# KELU1-0234.net
KiCad netlist of a schematic drawn in EAGLE
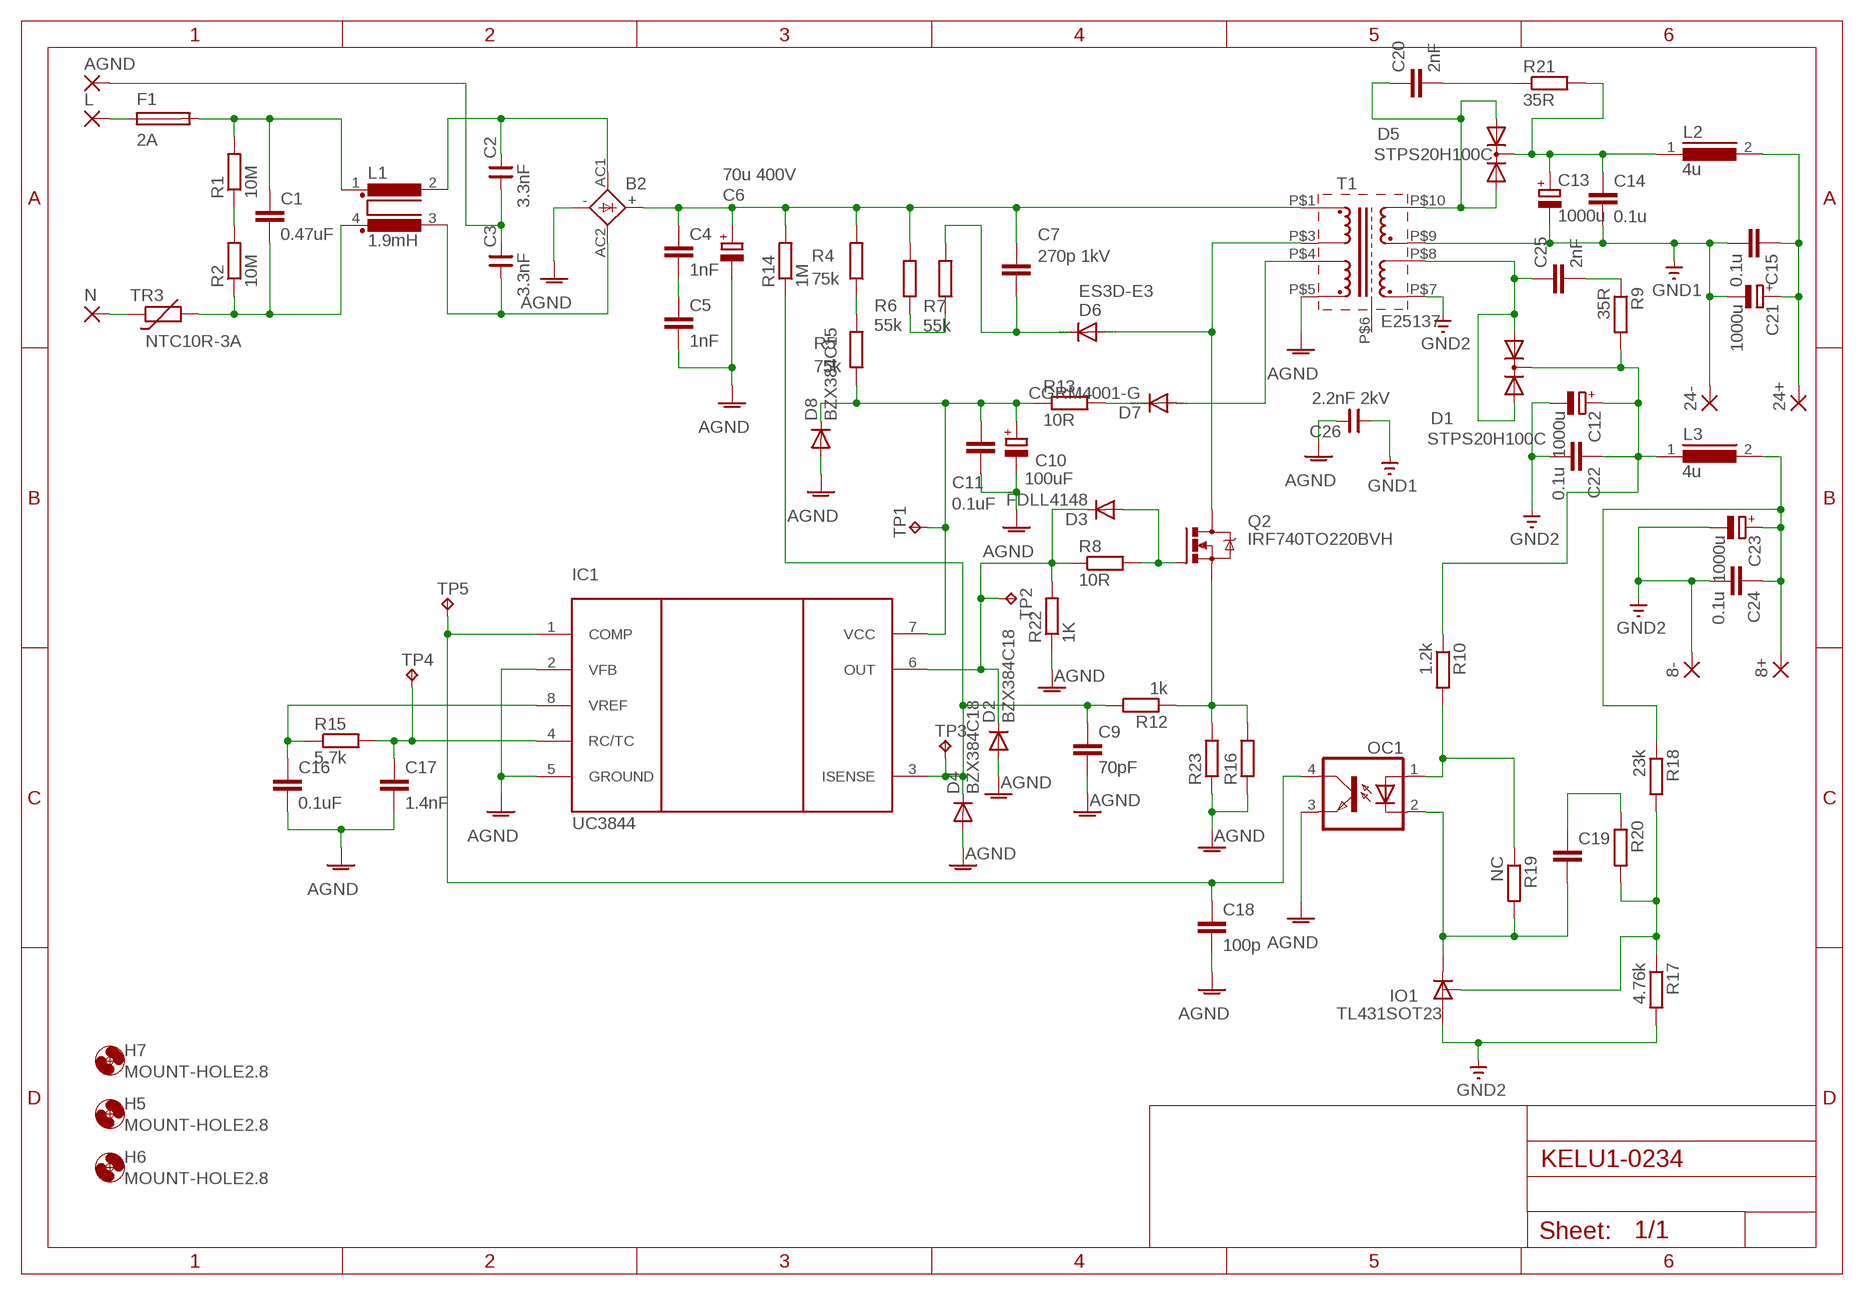
[diagram p0: schematic, sheet 1]

(export (version "E")
  (design (tool "Eeschema 10.0.6"))
  (components
    (comp (ref "8+")
      (value "3,17/1,1")
      (footprint "eagle-import:3,17_1,1")
      (libsource (lib "eagle-import") (part "3,17/1,1"))
    )
    (comp (ref "8-")
      (value "3,17/1,1")
      (footprint "eagle-import:3,17_1,1")
      (libsource (lib "eagle-import") (part "3,17/1,1"))
    )
    (comp (ref "24+")
      (value "3,17/1,1")
      (footprint "eagle-import:3,17_1,1")
      (libsource (lib "eagle-import") (part "3,17/1,1"))
    )
    (comp (ref "24-")
      (value "3,17/1,1")
      (footprint "eagle-import:3,17_1,1")
      (libsource (lib "eagle-import") (part "3,17/1,1"))
    )
    (comp (ref "AGND")
      (value "3,17/1,1")
      (footprint "eagle-import:3,17_1,1")
      (libsource (lib "eagle-import") (part "3,17/1,1"))
    )
    (comp (ref "B2")
      (value "2KBP")
      (footprint "eagle-import:2KBP")
      (libsource (lib "eagle-import") (part "2KBP"))
    )
    (comp (ref "C1")
      (value "0.47uF")
      (footprint "eagle-import:C15B5")
      (libsource (lib "eagle-import") (part "C15/5"))
    )
    (comp (ref "C2")
      (value "3.3nF")
      (footprint "eagle-import:C085-110X050")
      (libsource (lib "eagle-import") (part "CNP-C085-110X050"))
    )
    (comp (ref "C3")
      (value "3.3nF")
      (footprint "eagle-import:C080-110X045")
      (libsource (lib "eagle-import") (part "CNP-C080-110X045"))
    )
    (comp (ref "C4")
      (value "1nF")
      (footprint "eagle-import:C1206K")
      (libsource (lib "eagle-import") (part "C-EUC1206K"))
    )
    (comp (ref "C5")
      (value "1nF")
      (footprint "eagle-import:C1206K")
      (libsource (lib "eagle-import") (part "C-EUC1206K"))
    )
    (comp (ref "C6")
      (value "70u 400V")
      (footprint "eagle-import:E7,5-16")
      (libsource (lib "eagle-import") (part "CPOL-EUE7.5-16"))
    )
    (comp (ref "C7")
      (value "270p 1kV")
      (footprint "eagle-import:C1206K")
      (libsource (lib "eagle-import") (part "C-EUC1206K"))
    )
    (comp (ref "C9")
      (value "70pF")
      (footprint "eagle-import:C0805K")
      (libsource (lib "eagle-import") (part "resistor_C-EUC0805K"))
    )
    (comp (ref "C10")
      (value "100uF")
      (footprint "eagle-import:E5-5")
      (libsource (lib "eagle-import") (part "resistor_CPOL-EUE5-5"))
    )
    (comp (ref "C11")
      (value "0.1uF")
      (footprint "eagle-import:C0805K")
      (libsource (lib "eagle-import") (part "resistor_C-EUC0805K"))
    )
    (comp (ref "C12")
      (value "1000u")
      (footprint "eagle-import:E3,5-8")
      (libsource (lib "eagle-import") (part "resistor_CPOL-EUE3.5-8"))
    )
    (comp (ref "C13")
      (value "1000u")
      (footprint "eagle-import:E3,5-8")
      (libsource (lib "eagle-import") (part "resistor_CPOL-EUE3.5-8"))
    )
    (comp (ref "C14")
      (value "0.1u")
      (footprint "eagle-import:C0805K")
      (libsource (lib "eagle-import") (part "resistor_C-EUC0805K"))
    )
    (comp (ref "C15")
      (value "0.1u")
      (footprint "eagle-import:C0805K")
      (libsource (lib "eagle-import") (part "resistor_C-EUC0805K"))
    )
    (comp (ref "C16")
      (value "0.1uF")
      (footprint "eagle-import:C0805K")
      (libsource (lib "eagle-import") (part "resistor_C-EUC0805K"))
    )
    (comp (ref "C17")
      (value "1.4nF")
      (footprint "eagle-import:C0805K")
      (libsource (lib "eagle-import") (part "resistor_C-EUC0805K"))
    )
    (comp (ref "C18")
      (value "100p")
      (footprint "eagle-import:C0805K")
      (libsource (lib "eagle-import") (part "resistor_C-EUC0805K"))
    )
    (comp (ref "C19")
      (value "C-EUC0805K")
      (footprint "eagle-import:C0805K")
      (libsource (lib "eagle-import") (part "resistor_C-EUC0805K"))
    )
    (comp (ref "C20")
      (value "2nF")
      (footprint "eagle-import:C1206K")
      (libsource (lib "eagle-import") (part "C-EUC1206K"))
    )
    (comp (ref "C21")
      (value "1000u")
      (footprint "eagle-import:E3,5-8")
      (libsource (lib "eagle-import") (part "resistor_CPOL-EUE3.5-8"))
    )
    (comp (ref "C22")
      (value "0.1u")
      (footprint "eagle-import:C0805K")
      (libsource (lib "eagle-import") (part "resistor_C-EUC0805K"))
    )
    (comp (ref "C23")
      (value "1000u")
      (footprint "eagle-import:E3,5-8")
      (libsource (lib "eagle-import") (part "resistor_CPOL-EUE3.5-8"))
    )
    (comp (ref "C24")
      (value "0.1u")
      (footprint "eagle-import:C0805K")
      (libsource (lib "eagle-import") (part "resistor_C-EUC0805K"))
    )
    (comp (ref "C25")
      (value "2nF")
      (footprint "eagle-import:C1206K")
      (libsource (lib "eagle-import") (part "C-EUC1206K"))
    )
    (comp (ref "C26")
      (value "2.2nF 2kV")
      (footprint "eagle-import:C080-110X045")
      (libsource (lib "eagle-import") (part "CNP-C080-110X045"))
    )
    (comp (ref "D1")
      (value "STPS20H100C")
      (footprint "eagle-import:TO220ABS")
      (libsource (lib "eagle-import") (part "BYV32"))
    )
    (comp (ref "D2")
      (value "BZX384C18")
      (footprint "eagle-import:SOD323-W")
      (libsource (lib "eagle-import") (part "diode-1_DIODE-SOD323-W"))
    )
    (comp (ref "D3")
      (value "FDLL4148")
      (footprint "eagle-import:MINIMELF")
      (libsource (lib "eagle-import") (part "diode-1_DIODE-MINIMELF"))
    )
    (comp (ref "D4")
      (value "BZX384C18")
      (footprint "eagle-import:SOD323-W")
      (libsource (lib "eagle-import") (part "diode-1_DIODE-SOD323-W"))
    )
    (comp (ref "D5")
      (value "STPS20H100C")
      (footprint "eagle-import:TO220ABS")
      (libsource (lib "eagle-import") (part "BYV32"))
    )
    (comp (ref "D6")
      (value "ES3D-E3")
      (footprint "eagle-import:SMC")
      (libsource (lib "eagle-import") (part "DIODE-SMC"))
    )
    (comp (ref "D7")
      (value "CGRM4001-G")
      (footprint "eagle-import:SOD-123_MINI-SMA")
      (libsource (lib "eagle-import") (part "CGRM400-G1"))
    )
    (comp (ref "D8")
      (value "BZX384C15")
      (footprint "eagle-import:SOD323-W")
      (libsource (lib "eagle-import") (part "diode-1_DIODE-SOD323-W"))
    )
    (comp (ref "F1")
      (value "2A")
      (footprint "eagle-import:TE5")
      (libsource (lib "eagle-import") (part "FUSETE5"))
    )
    (comp (ref "H5")
      (value "MOUNT-HOLE2.8")
      (footprint "eagle-import:2,8")
      (libsource (lib "eagle-import") (part "MOUNT-HOLE2.8"))
    )
    (comp (ref "H6")
      (value "MOUNT-HOLE2.8")
      (footprint "eagle-import:2,8")
      (libsource (lib "eagle-import") (part "MOUNT-HOLE2.8"))
    )
    (comp (ref "H7")
      (value "MOUNT-HOLE2.8")
      (footprint "eagle-import:2,8")
      (libsource (lib "eagle-import") (part "MOUNT-HOLE2.8"))
    )
    (comp (ref "IC1")
      (value "UC3844")
      (footprint "eagle-import:SOIC08")
      (libsource (lib "eagle-import") (part "UC3844"))
    )
    (comp (ref "IO1")
      (value "TL431SOT23")
      (footprint "eagle-import:SOT23")
      (fields (field (name "MPN") "TL431BFDT"))
      (libsource (lib "eagle-import") (part "TL431SOT23"))
    )
    (comp (ref "L")
      (value "3,17/1,1")
      (footprint "eagle-import:3,17_1,1")
      (libsource (lib "eagle-import") (part "3,17/1,1"))
    )
    (comp (ref "L1")
      (value "1.9mH")
      (footprint "eagle-import:MFE")
      (libsource (lib "eagle-import") (part "MFE"))
    )
    (comp (ref "L2")
      (value "4u")
      (footprint "eagle-import:82114R")
      (libsource (lib "eagle-import") (part "82114R"))
    )
    (comp (ref "L3")
      (value "4u")
      (footprint "eagle-import:82114R")
      (libsource (lib "eagle-import") (part "82114R"))
    )
    (comp (ref "N")
      (value "3,17/1,1")
      (footprint "eagle-import:3,17_1,1")
      (libsource (lib "eagle-import") (part "3,17/1,1"))
    )
    (comp (ref "OC1")
      (value "PC817")
      (footprint "eagle-import:DIL04")
      (libsource (lib "eagle-import") (part "PC817"))
    )
    (comp (ref "Q2")
      (value "IRF740TO220BVH")
      (footprint "eagle-import:TO220BVH")
      (libsource (lib "eagle-import") (part "IRF740TO220BVH"))
    )
    (comp (ref "R1")
      (value "10M")
      (footprint "eagle-import:M1206")
      (libsource (lib "eagle-import") (part "R-EU_M1206"))
    )
    (comp (ref "R2")
      (value "10M")
      (footprint "eagle-import:M1206")
      (libsource (lib "eagle-import") (part "R-EU_M1206"))
    )
    (comp (ref "R4")
      (value "75k")
      (footprint "eagle-import:M1206")
      (libsource (lib "eagle-import") (part "R-EU_M1206"))
    )
    (comp (ref "R5")
      (value "75k")
      (footprint "eagle-import:M1206")
      (libsource (lib "eagle-import") (part "R-EU_M1206"))
    )
    (comp (ref "R6")
      (value "55k")
      (footprint "eagle-import:M1206")
      (libsource (lib "eagle-import") (part "R-EU_M1206"))
    )
    (comp (ref "R7")
      (value "55k")
      (footprint "eagle-import:M1206")
      (libsource (lib "eagle-import") (part "R-EU_M1206"))
    )
    (comp (ref "R8")
      (value "10R")
      (footprint "eagle-import:M1206")
      (libsource (lib "eagle-import") (part "resistor_R-EU_M1206"))
    )
    (comp (ref "R9")
      (value "35R")
      (footprint "eagle-import:M1206")
      (libsource (lib "eagle-import") (part "R-EU_M1206"))
    )
    (comp (ref "R10")
      (value "1.2k")
      (footprint "eagle-import:R0805W")
      (libsource (lib "eagle-import") (part "resistor_R-EU_R0805W"))
    )
    (comp (ref "R12")
      (value "1k")
      (footprint "eagle-import:R0805W")
      (libsource (lib "eagle-import") (part "resistor_R-EU_R0805W"))
    )
    (comp (ref "R13")
      (value "10R")
      (footprint "eagle-import:R0805W")
      (libsource (lib "eagle-import") (part "resistor_R-EU_R0805W"))
    )
    (comp (ref "R14")
      (value "1M")
      (footprint "eagle-import:M1206")
      (libsource (lib "eagle-import") (part "R-EU_M1206"))
    )
    (comp (ref "R15")
      (value "5.7k")
      (footprint "eagle-import:R0805W")
      (libsource (lib "eagle-import") (part "resistor_R-EU_R0805W"))
    )
    (comp (ref "R16")
      (value "R-EU_R2512")
      (footprint "eagle-import:R2512")
      (libsource (lib "eagle-import") (part "R-EU_R2512"))
    )
    (comp (ref "R17")
      (value "4.76k")
      (footprint "eagle-import:R0805W")
      (libsource (lib "eagle-import") (part "resistor_R-EU_R0805W"))
    )
    (comp (ref "R18")
      (value "23k")
      (footprint "eagle-import:R0805W")
      (libsource (lib "eagle-import") (part "resistor_R-EU_R0805W"))
    )
    (comp (ref "R19")
      (value "NC")
      (footprint "eagle-import:R0805W")
      (libsource (lib "eagle-import") (part "resistor_R-EU_R0805W"))
    )
    (comp (ref "R20")
      (value "R-EU_R0805W")
      (footprint "eagle-import:R0805W")
      (libsource (lib "eagle-import") (part "resistor_R-EU_R0805W"))
    )
    (comp (ref "R21")
      (value "35R")
      (footprint "eagle-import:M1206")
      (libsource (lib "eagle-import") (part "R-EU_M1206"))
    )
    (comp (ref "R22")
      (value "1K")
      (footprint "eagle-import:M1206")
      (libsource (lib "eagle-import") (part "resistor_R-EU_M1206"))
    )
    (comp (ref "R23")
      (value "R-EU_R2512")
      (footprint "eagle-import:R2512")
      (libsource (lib "eagle-import") (part "R-EU_R2512"))
    )
    (comp (ref "T1")
      (value "E25137")
      (footprint "eagle-import:E25137")
      (libsource (lib "eagle-import") (part "E25137"))
    )
    (comp (ref "TP1")
      (value "TPB1,27")
      (footprint "eagle-import:B1,27")
      (libsource (lib "eagle-import") (part "TPB1,27"))
    )
    (comp (ref "TP2")
      (value "TPB1,27")
      (footprint "eagle-import:B1,27")
      (libsource (lib "eagle-import") (part "TPB1,27"))
    )
    (comp (ref "TP3")
      (value "TPB1,27")
      (footprint "eagle-import:B1,27")
      (libsource (lib "eagle-import") (part "TPB1,27"))
    )
    (comp (ref "TP4")
      (value "TPB1,27")
      (footprint "eagle-import:B1,27")
      (libsource (lib "eagle-import") (part "TPB1,27"))
    )
    (comp (ref "TP5")
      (value "TPB1,27")
      (footprint "eagle-import:B1,27")
      (libsource (lib "eagle-import") (part "TPB1,27"))
    )
    (comp (ref "TR3")
      (value "NTC10R-3A")
      (footprint "eagle-import:R-5")
      (libsource (lib "eagle-import") (part "THERMISTOR-5"))
    )
  )
  (nets
    (net (code "1") (name "AGND") (class "Default")
      (node (ref "B2") (pin "-") (pinfunction "-_-") (pintype "passive"))
      (node (ref "C10") (pin "-") (pinfunction "-_-") (pintype "passive"))
      (node (ref "C11") (pin "2") (pinfunction "2_2") (pintype "passive"))
      (node (ref "C16") (pin "2") (pinfunction "2_2") (pintype "passive"))
      (node (ref "C17") (pin "2") (pinfunction "2_2") (pintype "passive"))
      (node (ref "C18") (pin "2") (pinfunction "2_2") (pintype "passive"))
      (node (ref "C26") (pin "2") (pinfunction "2_2") (pintype "passive"))
      (node (ref "C5") (pin "2") (pinfunction "2_2") (pintype "passive"))
      (node (ref "C6") (pin "-") (pinfunction "-_-") (pintype "passive"))
      (node (ref "C9") (pin "2") (pinfunction "2_2") (pintype "passive"))
      (node (ref "D2") (pin "A") (pinfunction "A_A") (pintype "passive"))
      (node (ref "D4") (pin "A") (pinfunction "A_A") (pintype "passive"))
      (node (ref "D8") (pin "A") (pinfunction "A_A") (pintype "passive"))
      (node (ref "IC1") (pin "2") (pinfunction "VFB_2") (pintype "bidirectional"))
      (node (ref "IC1") (pin "5") (pinfunction "GROUND_5") (pintype "bidirectional"))
      (node (ref "OC1") (pin "3") (pinfunction "EMIT_3") (pintype "passive"))
      (node (ref "R16") (pin "1") (pinfunction "1_1") (pintype "passive"))
      (node (ref "R22") (pin "1") (pinfunction "1_1") (pintype "passive"))
      (node (ref "R23") (pin "1") (pinfunction "1_1") (pintype "passive"))
      (node (ref "T1") (pin "P$5") (pinfunction "5_P$5") (pintype "passive"))
    )
    (net (code "2") (name "GND1") (class "Default")
      (node (ref "24-") (pin "1") (pinfunction "P_1") (pintype "passive"))
      (node (ref "C13") (pin "-") (pinfunction "-_-") (pintype "passive"))
      (node (ref "C14") (pin "2") (pinfunction "2_2") (pintype "passive"))
      (node (ref "C15") (pin "2") (pinfunction "2_2") (pintype "passive"))
      (node (ref "C21") (pin "-") (pinfunction "-_-") (pintype "passive"))
      (node (ref "C26") (pin "1") (pinfunction "1_1") (pintype "passive"))
      (node (ref "T1") (pin "P$9") (pinfunction "9_P$9") (pintype "passive"))
    )
    (net (code "3") (name "GND2") (class "Default")
      (node (ref "8-") (pin "1") (pinfunction "P_1") (pintype "passive"))
      (node (ref "C12") (pin "-") (pinfunction "-_-") (pintype "passive"))
      (node (ref "C22") (pin "2") (pinfunction "2_2") (pintype "passive"))
      (node (ref "C23") (pin "-") (pinfunction "-_-") (pintype "passive"))
      (node (ref "C24") (pin "2") (pinfunction "2_2") (pintype "passive"))
      (node (ref "IO1") (pin "3") (pinfunction "A_3") (pintype "bidirectional"))
      (node (ref "R17") (pin "2") (pinfunction "2_2") (pintype "passive"))
      (node (ref "T1") (pin "P$7") (pinfunction "7_P$7") (pintype "passive"))
    )
    (net (code "4") (name "Net-(8+-P)") (class "Default")
      (node (ref "8+") (pin "1") (pinfunction "P_1") (pintype "passive"))
      (node (ref "C23") (pin "+") (pinfunction "+_+") (pintype "passive"))
      (node (ref "C24") (pin "1") (pinfunction "1_1") (pintype "passive"))
      (node (ref "L3") (pin "2") (pinfunction "2_2") (pintype "passive"))
      (node (ref "R18") (pin "1") (pinfunction "1_1") (pintype "passive"))
    )
    (net (code "5") (name "Net-(24+-P)") (class "Default")
      (node (ref "24+") (pin "1") (pinfunction "P_1") (pintype "passive"))
      (node (ref "C15") (pin "1") (pinfunction "1_1") (pintype "passive"))
      (node (ref "C21") (pin "+") (pinfunction "+_+") (pintype "passive"))
      (node (ref "L2") (pin "2") (pinfunction "2_2") (pintype "passive"))
    )
    (net (code "6") (name "Net-(AGND-P)") (class "Default")
      (node (ref "AGND") (pin "1") (pinfunction "P_1") (pintype "passive"))
      (node (ref "C2") (pin "1") (pinfunction "1_1") (pintype "passive"))
      (node (ref "C3") (pin "2") (pinfunction "2_2") (pintype "passive"))
    )
    (net (code "7") (name "Net-(B2-PadAC1)") (class "Default")
      (node (ref "B2") (pin "AC1") (pinfunction "AC1_AC1") (pintype "passive"))
      (node (ref "C2") (pin "2") (pinfunction "2_2") (pintype "passive"))
      (node (ref "L1") (pin "2") (pinfunction "2_2") (pintype "passive"))
    )
    (net (code "8") (name "Net-(C1-Pad1)") (class "Default")
      (node (ref "C1") (pin "1") (pinfunction "1_1") (pintype "passive"))
      (node (ref "F1") (pin "2") (pinfunction "2_2") (pintype "passive"))
      (node (ref "L1") (pin "1") (pinfunction "1_1") (pintype "passive"))
      (node (ref "R1") (pin "2") (pinfunction "2_2") (pintype "passive"))
    )
    (net (code "9") (name "Net-(C4-Pad2)") (class "Default")
      (node (ref "C4") (pin "2") (pinfunction "2_2") (pintype "passive"))
      (node (ref "C5") (pin "1") (pinfunction "1_1") (pintype "passive"))
    )
    (net (code "10") (name "Net-(C7-Pad2)") (class "Default")
      (node (ref "C7") (pin "2") (pinfunction "2_2") (pintype "passive"))
      (node (ref "D6") (pin "C") (pinfunction "C_C") (pintype "passive"))
      (node (ref "R7") (pin "2") (pinfunction "2_2") (pintype "passive"))
    )
    (net (code "11") (name "Net-(C12-Pad+)") (class "Default")
      (node (ref "C12") (pin "+") (pinfunction "+_+") (pintype "passive"))
      (node (ref "C22") (pin "1") (pinfunction "1_1") (pintype "passive"))
      (node (ref "D1") (pin "C") (pinfunction "C_C") (pintype "passive"))
      (node (ref "L3") (pin "1") (pinfunction "1_1") (pintype "passive"))
      (node (ref "R10") (pin "1") (pinfunction "1_1") (pintype "passive"))
      (node (ref "R9") (pin "2") (pinfunction "2_2") (pintype "passive"))
    )
    (net (code "12") (name "Net-(C13-Pad+)") (class "Default")
      (node (ref "C13") (pin "+") (pinfunction "+_+") (pintype "passive"))
      (node (ref "C14") (pin "1") (pinfunction "1_1") (pintype "passive"))
      (node (ref "D5") (pin "C") (pinfunction "C_C") (pintype "passive"))
      (node (ref "L2") (pin "1") (pinfunction "1_1") (pintype "passive"))
      (node (ref "R21") (pin "2") (pinfunction "2_2") (pintype "passive"))
    )
    (net (code "13") (name "Net-(C19-Pad1)") (class "Default")
      (node (ref "C19") (pin "1") (pinfunction "1_1") (pintype "passive"))
      (node (ref "R20") (pin "1") (pinfunction "1_1") (pintype "passive"))
    )
    (net (code "14") (name "Net-(C20-Pad2)") (class "Default")
      (node (ref "C20") (pin "2") (pinfunction "2_2") (pintype "passive"))
      (node (ref "R21") (pin "1") (pinfunction "1_1") (pintype "passive"))
    )
    (net (code "15") (name "Net-(C25-Pad2)") (class "Default")
      (node (ref "C25") (pin "2") (pinfunction "2_2") (pintype "passive"))
      (node (ref "R9") (pin "1") (pinfunction "1_1") (pintype "passive"))
    )
    (net (code "16") (name "Net-(D3-PadA)") (class "Default")
      (node (ref "D3") (pin "A") (pinfunction "A_A") (pintype "passive"))
      (node (ref "Q2") (pin "G") (pinfunction "G_G") (pintype "passive"))
      (node (ref "R8") (pin "2") (pinfunction "2_2") (pintype "passive"))
    )
    (net (code "17") (name "Net-(D7-PadC)") (class "Default")
      (node (ref "D7") (pin "C") (pinfunction "C_C") (pintype "passive"))
      (node (ref "R13") (pin "2") (pinfunction "2_2") (pintype "passive"))
    )
    (net (code "18") (name "Net-(IC1-COMP)") (class "Default")
      (node (ref "C18") (pin "1") (pinfunction "1_1") (pintype "passive"))
      (node (ref "IC1") (pin "1") (pinfunction "COMP_1") (pintype "bidirectional"))
      (node (ref "OC1") (pin "4") (pinfunction "COL_4") (pintype "passive"))
      (node (ref "TP5") (pin "PP") (pinfunction "TP_PP") (pintype "input"))
    )
    (net (code "19") (name "Net-(IC1-ISENSE)") (class "Default")
      (node (ref "C9") (pin "1") (pinfunction "1_1") (pintype "passive"))
      (node (ref "D4") (pin "C") (pinfunction "C_C") (pintype "passive"))
      (node (ref "IC1") (pin "3") (pinfunction "ISENSE_3") (pintype "bidirectional"))
      (node (ref "R12") (pin "2") (pinfunction "2_2") (pintype "passive"))
      (node (ref "R14") (pin "1") (pinfunction "1_1") (pintype "passive"))
      (node (ref "TP3") (pin "PP") (pinfunction "TP_PP") (pintype "input"))
    )
    (net (code "20") (name "Net-(IC1-OUT)") (class "Default")
      (node (ref "D2") (pin "C") (pinfunction "C_C") (pintype "passive"))
      (node (ref "D3") (pin "C") (pinfunction "C_C") (pintype "passive"))
      (node (ref "IC1") (pin "6") (pinfunction "OUT_6") (pintype "bidirectional"))
      (node (ref "R22") (pin "2") (pinfunction "2_2") (pintype "passive"))
      (node (ref "R8") (pin "1") (pinfunction "1_1") (pintype "passive"))
      (node (ref "TP2") (pin "PP") (pinfunction "TP_PP") (pintype "input"))
    )
    (net (code "21") (name "Net-(IC1-RC{slash}TC)") (class "Default")
      (node (ref "C17") (pin "1") (pinfunction "1_1") (pintype "passive"))
      (node (ref "IC1") (pin "4") (pinfunction "RC/TC_4") (pintype "bidirectional"))
      (node (ref "R15") (pin "2") (pinfunction "2_2") (pintype "passive"))
      (node (ref "TP4") (pin "PP") (pinfunction "TP_PP") (pintype "input"))
    )
    (net (code "22") (name "Net-(IC1-VCC)") (class "Default")
      (node (ref "C10") (pin "+") (pinfunction "+_+") (pintype "passive"))
      (node (ref "C11") (pin "1") (pinfunction "1_1") (pintype "passive"))
      (node (ref "D8") (pin "C") (pinfunction "C_C") (pintype "passive"))
      (node (ref "IC1") (pin "7") (pinfunction "VCC_7") (pintype "bidirectional"))
      (node (ref "R13") (pin "1") (pinfunction "1_1") (pintype "passive"))
      (node (ref "R5") (pin "1") (pinfunction "1_1") (pintype "passive"))
      (node (ref "TP1") (pin "PP") (pinfunction "TP_PP") (pintype "input"))
    )
    (net (code "23") (name "Net-(IC1-VREF)") (class "Default")
      (node (ref "C16") (pin "1") (pinfunction "1_1") (pintype "passive"))
      (node (ref "IC1") (pin "8") (pinfunction "VREF_8") (pintype "bidirectional"))
      (node (ref "R15") (pin "1") (pinfunction "1_1") (pintype "passive"))
    )
    (net (code "24") (name "Net-(IO1-C)") (class "Default")
      (node (ref "C19") (pin "2") (pinfunction "2_2") (pintype "passive"))
      (node (ref "IO1") (pin "1") (pinfunction "C_1") (pintype "bidirectional"))
      (node (ref "OC1") (pin "2") (pinfunction "C_2") (pintype "passive"))
      (node (ref "R19") (pin "2") (pinfunction "2_2") (pintype "passive"))
    )
    (net (code "25") (name "Net-(IO1-R)") (class "Default")
      (node (ref "IO1") (pin "2") (pinfunction "R_2") (pintype "bidirectional"))
      (node (ref "R17") (pin "1") (pinfunction "1_1") (pintype "passive"))
      (node (ref "R18") (pin "2") (pinfunction "2_2") (pintype "passive"))
      (node (ref "R20") (pin "2") (pinfunction "2_2") (pintype "passive"))
    )
    (net (code "26") (name "Net-(L-P)") (class "Default")
      (node (ref "F1") (pin "1") (pinfunction "1_1") (pintype "passive"))
      (node (ref "L") (pin "1") (pinfunction "P_1") (pintype "passive"))
    )
    (net (code "27") (name "Net-(L1-3)") (class "Default")
      (node (ref "C1") (pin "2") (pinfunction "2_2") (pintype "passive"))
      (node (ref "L1") (pin "4") (pinfunction "3_4") (pintype "passive"))
      (node (ref "R2") (pin "1") (pinfunction "1_1") (pintype "passive"))
      (node (ref "TR3") (pin "2") (pinfunction "2_2") (pintype "passive"))
    )
    (net (code "28") (name "Net-(L1-4)") (class "Default")
      (node (ref "B2") (pin "AC2") (pinfunction "AC2_AC2") (pintype "passive"))
      (node (ref "C3") (pin "1") (pinfunction "1_1") (pintype "passive"))
      (node (ref "L1") (pin "3") (pinfunction "4_3") (pintype "passive"))
    )
    (net (code "29") (name "Net-(N-P)") (class "Default")
      (node (ref "N") (pin "1") (pinfunction "P_1") (pintype "passive"))
      (node (ref "TR3") (pin "1") (pinfunction "1_1") (pintype "passive"))
    )
    (net (code "30") (name "Net-(OC1-A)") (class "Default")
      (node (ref "OC1") (pin "1") (pinfunction "A_1") (pintype "passive"))
      (node (ref "R10") (pin "2") (pinfunction "2_2") (pintype "passive"))
      (node (ref "R19") (pin "1") (pinfunction "1_1") (pintype "passive"))
    )
    (net (code "31") (name "Net-(Q2-PadS)") (class "Default")
      (node (ref "Q2") (pin "S") (pinfunction "S_S") (pintype "passive"))
      (node (ref "R12") (pin "1") (pinfunction "1_1") (pintype "passive"))
      (node (ref "R16") (pin "2") (pinfunction "2_2") (pintype "passive"))
      (node (ref "R23") (pin "2") (pinfunction "2_2") (pintype "passive"))
    )
    (net (code "32") (name "Net-(R1-Pad1)") (class "Default")
      (node (ref "R1") (pin "1") (pinfunction "1_1") (pintype "passive"))
      (node (ref "R2") (pin "2") (pinfunction "2_2") (pintype "passive"))
    )
    (net (code "33") (name "Net-(R4-Pad1)") (class "Default")
      (node (ref "R4") (pin "1") (pinfunction "1_1") (pintype "passive"))
      (node (ref "R5") (pin "2") (pinfunction "2_2") (pintype "passive"))
    )
    (net (code "34") (name "Net-(R6-Pad1)") (class "Default")
      (node (ref "R6") (pin "1") (pinfunction "1_1") (pintype "passive"))
      (node (ref "R7") (pin "1") (pinfunction "1_1") (pintype "passive"))
    )
    (net (code "35") (name "Net-(T1-1)") (class "Default")
      (node (ref "B2") (pin "+") (pinfunction "+_+") (pintype "passive"))
      (node (ref "C4") (pin "1") (pinfunction "1_1") (pintype "passive"))
      (node (ref "C6") (pin "+") (pinfunction "+_+") (pintype "passive"))
      (node (ref "C7") (pin "1") (pinfunction "1_1") (pintype "passive"))
      (node (ref "R14") (pin "2") (pinfunction "2_2") (pintype "passive"))
      (node (ref "R4") (pin "2") (pinfunction "2_2") (pintype "passive"))
      (node (ref "R6") (pin "2") (pinfunction "2_2") (pintype "passive"))
      (node (ref "T1") (pin "P$1") (pinfunction "1_P$1") (pintype "passive"))
    )
    (net (code "36") (name "Net-(T1-3)") (class "Default")
      (node (ref "D6") (pin "A") (pinfunction "A_A") (pintype "passive"))
      (node (ref "Q2") (pin "D") (pinfunction "D_D") (pintype "passive"))
      (node (ref "T1") (pin "P$3") (pinfunction "3_P$3") (pintype "passive"))
    )
    (net (code "37") (name "Net-(T1-4)") (class "Default")
      (node (ref "D7") (pin "A") (pinfunction "A_A") (pintype "passive"))
      (node (ref "T1") (pin "P$4") (pinfunction "4_P$4") (pintype "passive"))
    )
    (net (code "38") (name "Net-(T1-8)") (class "Default")
      (node (ref "C25") (pin "1") (pinfunction "1_1") (pintype "passive"))
      (node (ref "D1") (pin "A1") (pinfunction "A1_A1") (pintype "passive"))
      (node (ref "D1") (pin "A2") (pinfunction "A2_A2") (pintype "passive"))
      (node (ref "T1") (pin "P$8") (pinfunction "8_P$8") (pintype "passive"))
    )
    (net (code "39") (name "Net-(T1-10)") (class "Default")
      (node (ref "C20") (pin "1") (pinfunction "1_1") (pintype "passive"))
      (node (ref "D5") (pin "A1") (pinfunction "A1_A1") (pintype "passive"))
      (node (ref "D5") (pin "A2") (pinfunction "A2_A2") (pintype "passive"))
      (node (ref "T1") (pin "P$10") (pinfunction "10_P$10") (pintype "passive"))
    )
    (net (code "40") (name "unconnected-(T1-6-PadP$6)") (class "Default")
      (node (ref "T1") (pin "P$6") (pinfunction "6_P$6") (pintype "passive"))
    )
  )
)
